# Sheet1.net
KiCad netlist of a schematic drawn in Altium Designer
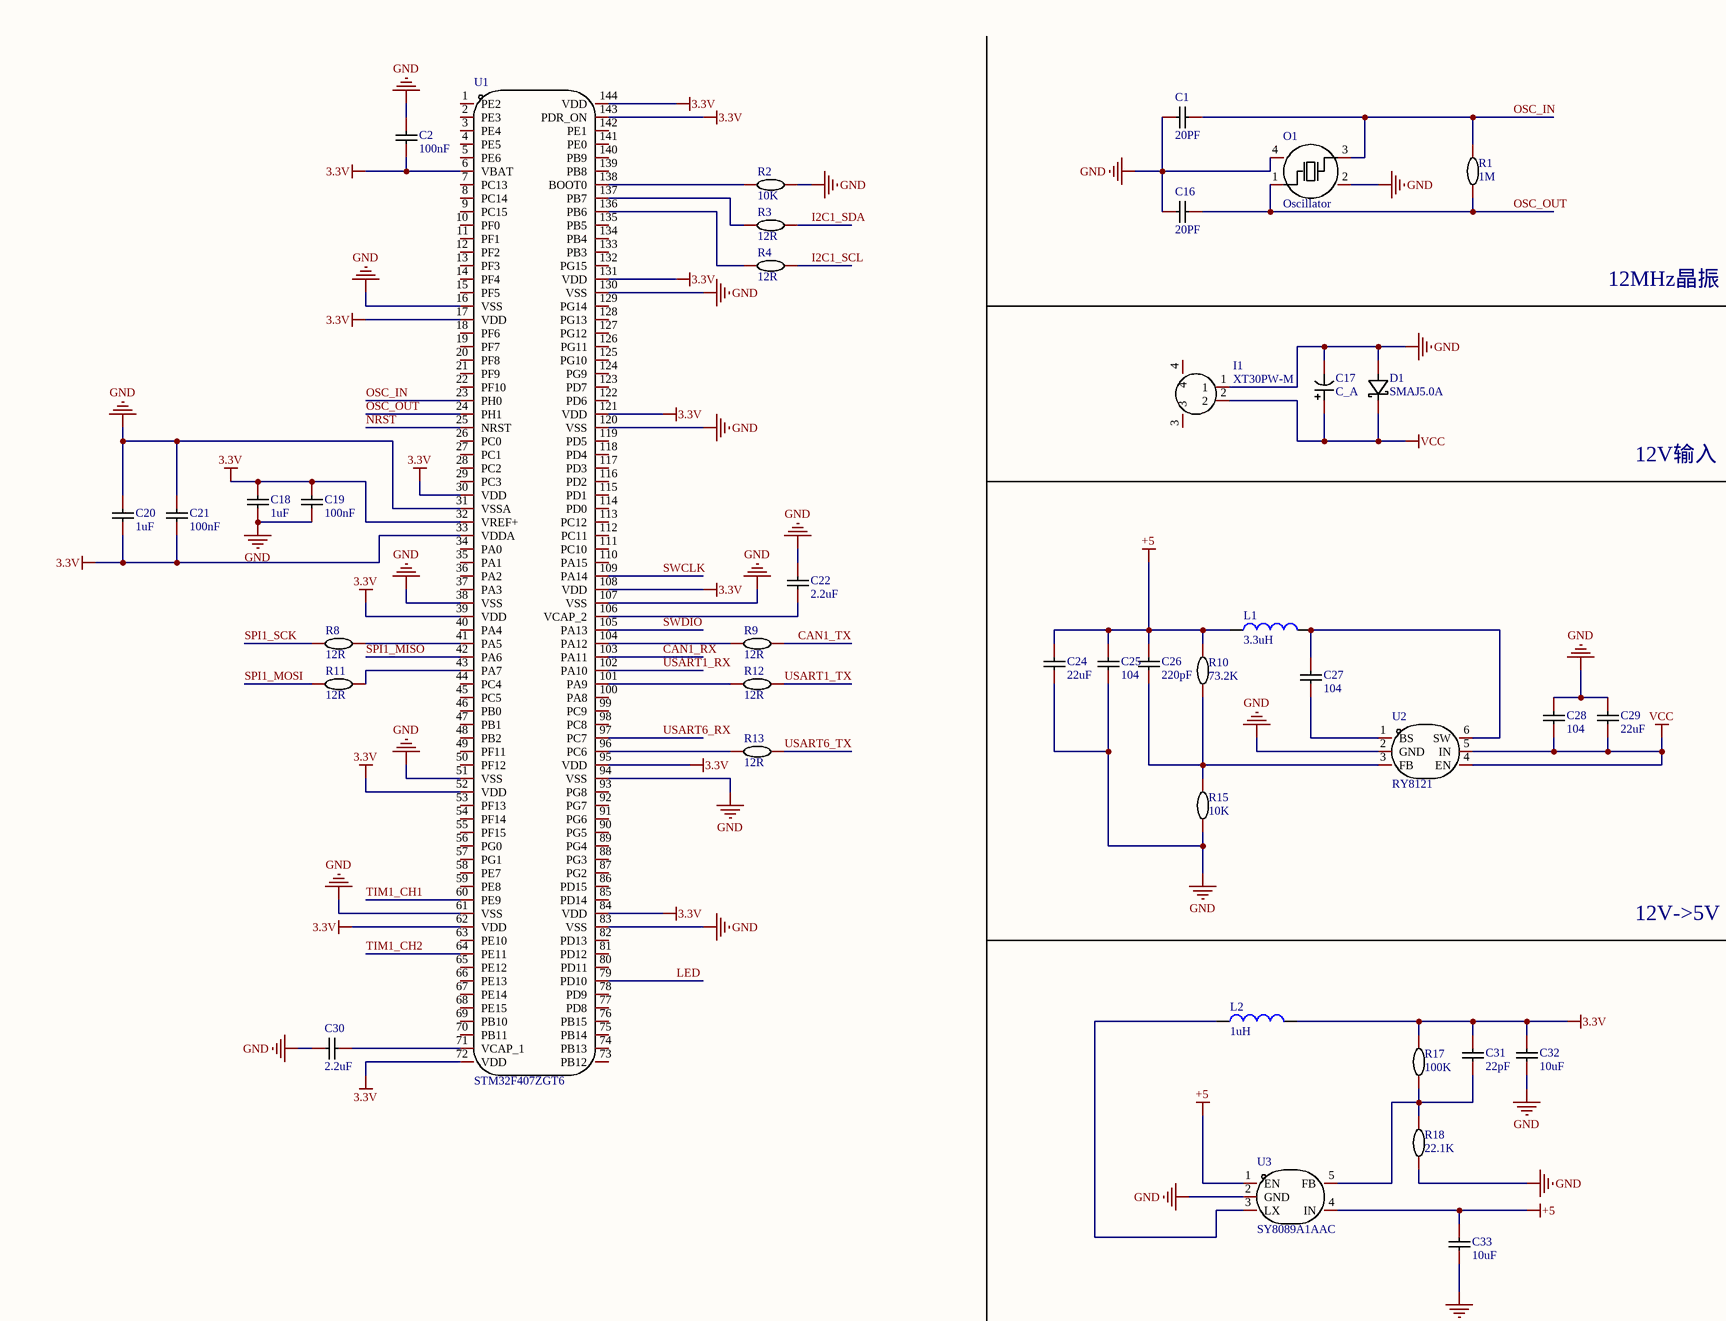
[diagram p0: Sheet1.SchDoc, top left]
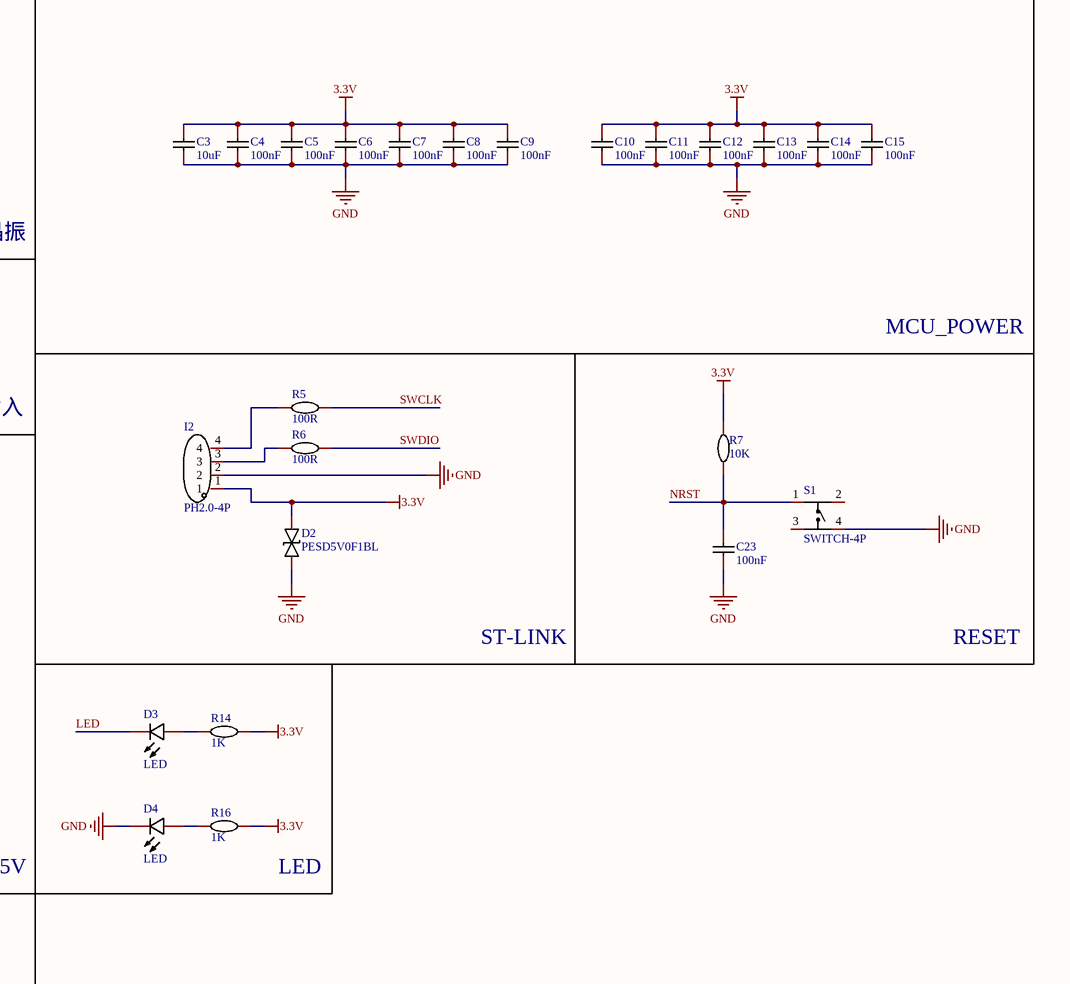
[diagram p1: Sheet1.SchDoc, top right]
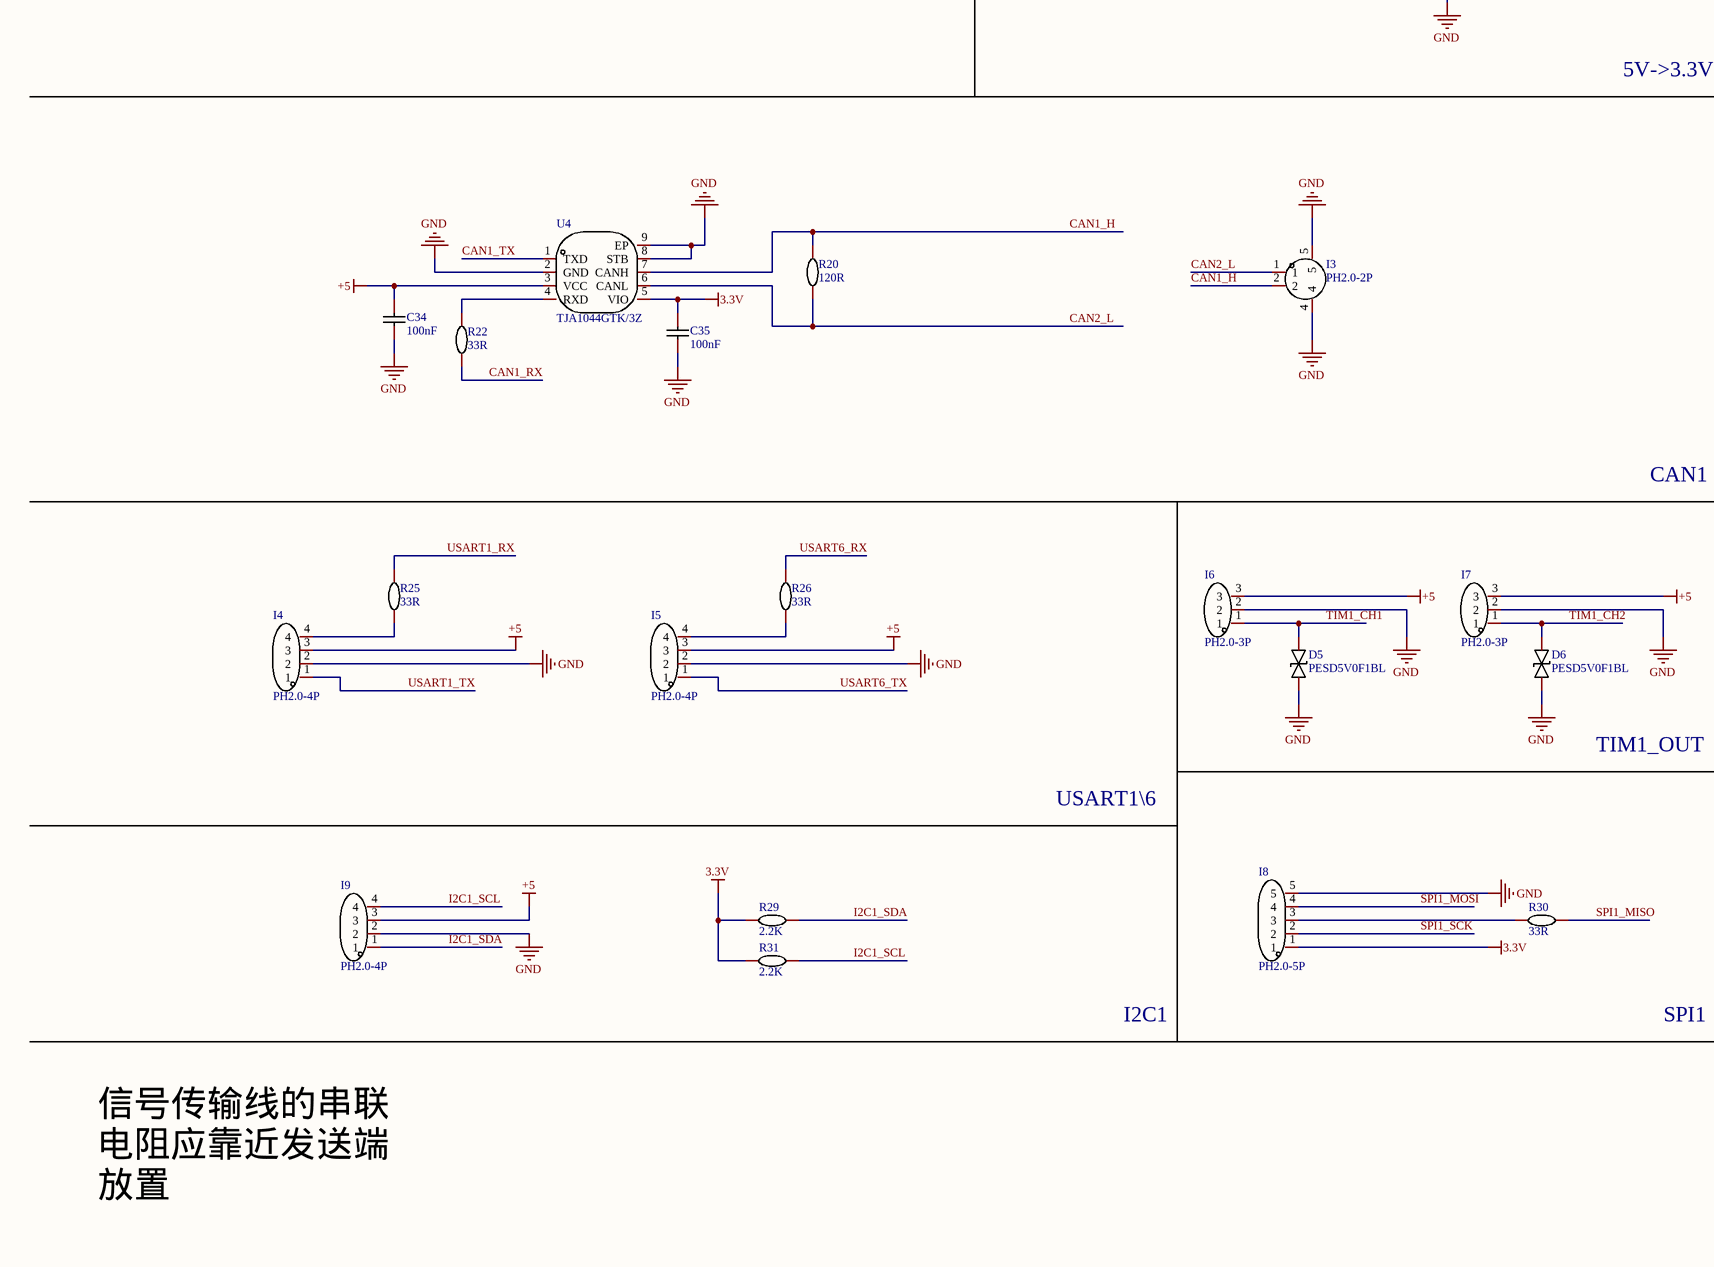
[diagram p2: Sheet1.SchDoc, bottom left]

(export (version "E")
  (design (tool "Eeschema 10.0.6"))
  (components
    (comp (ref "C1")
      (value "20PF")
      (footprint "C_0201")
      (description "贴片电容")
      (libsource (lib "My_Integrated_Library") (part "C"))
    )
    (comp (ref "C2")
      (value "100nF")
      (footprint "C_0201")
      (description "无极性贴片电容")
      (libsource (lib "My_Integrated_Library") (part "C"))
    )
    (comp (ref "C3")
      (value "10uF")
      (footprint "C_0201")
      (description "无极性贴片电容")
      (libsource (lib "My_Integrated_Library") (part "C"))
    )
    (comp (ref "C4")
      (value "100nF")
      (footprint "C_0201")
      (description "无极性贴片电容")
      (libsource (lib "My_Integrated_Library") (part "C"))
    )
    (comp (ref "C5")
      (value "100nF")
      (footprint "C_0201")
      (description "无极性贴片电容")
      (libsource (lib "My_Integrated_Library") (part "C"))
    )
    (comp (ref "C6")
      (value "100nF")
      (footprint "C_0201")
      (description "无极性贴片电容")
      (libsource (lib "My_Integrated_Library") (part "C"))
    )
    (comp (ref "C7")
      (value "100nF")
      (footprint "C_0201")
      (description "无极性贴片电容")
      (libsource (lib "My_Integrated_Library") (part "C"))
    )
    (comp (ref "C8")
      (value "100nF")
      (footprint "C_0201")
      (description "无极性贴片电容")
      (libsource (lib "My_Integrated_Library") (part "C"))
    )
    (comp (ref "C9")
      (value "100nF")
      (footprint "C_0201")
      (description "无极性贴片电容")
      (libsource (lib "My_Integrated_Library") (part "C"))
    )
    (comp (ref "C10")
      (value "100nF")
      (footprint "C_0201")
      (description "无极性贴片电容")
      (libsource (lib "My_Integrated_Library") (part "C"))
    )
    (comp (ref "C11")
      (value "100nF")
      (footprint "C_0201")
      (description "无极性贴片电容")
      (libsource (lib "My_Integrated_Library") (part "C"))
    )
    (comp (ref "C12")
      (value "100nF")
      (footprint "C_0201")
      (description "无极性贴片电容")
      (libsource (lib "My_Integrated_Library") (part "C"))
    )
    (comp (ref "C13")
      (value "100nF")
      (footprint "C_0201")
      (description "无极性贴片电容")
      (libsource (lib "My_Integrated_Library") (part "C"))
    )
    (comp (ref "C14")
      (value "100nF")
      (footprint "C_0201")
      (description "无极性贴片电容")
      (libsource (lib "My_Integrated_Library") (part "C"))
    )
    (comp (ref "C15")
      (value "100nF")
      (footprint "C_0201")
      (description "无极性贴片电容")
      (libsource (lib "My_Integrated_Library") (part "C"))
    )
    (comp (ref "C16")
      (value "20PF")
      (footprint "C_0201")
      (description "贴片电容")
      (libsource (lib "My_Integrated_Library") (part "C"))
    )
    (comp (ref "C17")
      (value "C_A")
      (footprint "C_8*10.5")
      (description "铝电解电容")
      (libsource (lib "My_Integrated_Library") (part "C_A"))
    )
    (comp (ref "C18")
      (value "1uF")
      (footprint "C_0201")
      (description "无极性贴片电容")
      (libsource (lib "My_Integrated_Library") (part "C"))
    )
    (comp (ref "C19")
      (value "100nF")
      (footprint "C_0201")
      (description "无极性贴片电容")
      (libsource (lib "My_Integrated_Library") (part "C"))
    )
    (comp (ref "C20")
      (value "1uF")
      (footprint "C_0201")
      (description "无极性贴片电容")
      (libsource (lib "My_Integrated_Library") (part "C"))
    )
    (comp (ref "C21")
      (value "100nF")
      (footprint "C_0201")
      (description "无极性贴片电容")
      (libsource (lib "My_Integrated_Library") (part "C"))
    )
    (comp (ref "C22")
      (value "2.2uF")
      (footprint "C_0201")
      (description "无极性贴片电容")
      (libsource (lib "My_Integrated_Library") (part "C"))
    )
    (comp (ref "C23")
      (value "100nF")
      (footprint "C_0402")
      (description "无极性贴片电容")
      (libsource (lib "My_Integrated_Library") (part "C"))
    )
    (comp (ref "C24")
      (value "22uF")
      (footprint "C_0402")
      (description "无极性贴片电容")
      (libsource (lib "My_Integrated_Library") (part "C"))
    )
    (comp (ref "C25")
      (value "104")
      (footprint "C_0402")
      (description "无极性贴片电容")
      (libsource (lib "My_Integrated_Library") (part "C"))
    )
    (comp (ref "C26")
      (value "220pF")
      (footprint "C_0603")
      (description "无极性贴片电容")
      (libsource (lib "My_Integrated_Library") (part "C"))
    )
    (comp (ref "C27")
      (value "104")
      (footprint "C_0402")
      (description "无极性贴片电容")
      (libsource (lib "My_Integrated_Library") (part "C"))
    )
    (comp (ref "C28")
      (value "104")
      (footprint "C_0402")
      (description "无极性贴片电容")
      (libsource (lib "My_Integrated_Library") (part "C"))
    )
    (comp (ref "C29")
      (value "22uF")
      (footprint "C_0402")
      (description "无极性贴片电容")
      (libsource (lib "My_Integrated_Library") (part "C"))
    )
    (comp (ref "C30")
      (value "2.2uF")
      (footprint "C_0201")
      (description "无极性贴片电容")
      (libsource (lib "My_Integrated_Library") (part "C"))
    )
    (comp (ref "C31")
      (value "22pF")
      (footprint "C_0603")
      (description "无极性贴片电容")
      (libsource (lib "My_Integrated_Library") (part "C"))
    )
    (comp (ref "C32")
      (value "10uF")
      (footprint "C_0603")
      (description "无极性贴片电容")
      (libsource (lib "My_Integrated_Library") (part "C"))
    )
    (comp (ref "C33")
      (value "10uF")
      (footprint "C_0603")
      (description "无极性贴片电容")
      (libsource (lib "My_Integrated_Library") (part "C"))
    )
    (comp (ref "C34")
      (value "100nF")
      (footprint "C_0402")
      (description "无极性贴片电容")
      (libsource (lib "My_Integrated_Library") (part "C"))
    )
    (comp (ref "C35")
      (value "100nF")
      (footprint "C_0402")
      (description "无极性贴片电容")
      (libsource (lib "My_Integrated_Library") (part "C"))
    )
    (comp (ref "D1")
      (value "SMAJ5.0A")
      (footprint "SMAJ5.0A")
      (description "TVS")
      (libsource (lib "My_Integrated_Library") (part "SMAJ5.0A"))
    )
    (comp (ref "D2")
      (value "PESD5V0F1BL")
      (footprint "PESD5V0F1BL")
      (description "双向TVS")
      (libsource (lib "My_Integrated_Library") (part "PESD5V0F1BL"))
    )
    (comp (ref "D3")
      (value "LED")
      (footprint "LED_0603")
      (description "发光二极管")
      (libsource (lib "My_Integrated_Library") (part "LED"))
    )
    (comp (ref "D4")
      (value "LED")
      (footprint "LED_0603")
      (description "发光二极管")
      (libsource (lib "My_Integrated_Library") (part "LED"))
    )
    (comp (ref "D5")
      (value "PESD5V0F1BL")
      (footprint "PESD5V0F1BL")
      (description "双向TVS")
      (libsource (lib "My_Integrated_Library") (part "PESD5V0F1BL"))
    )
    (comp (ref "D6")
      (value "PESD5V0F1BL")
      (footprint "PESD5V0F1BL")
      (description "双向TVS")
      (libsource (lib "My_Integrated_Library") (part "PESD5V0F1BL"))
    )
    (comp (ref "I1")
      (value "XT30PW-M")
      (footprint "XT30PW-M")
      (description "卧式公头")
      (libsource (lib "My_Integrated_Library") (part "XT30PW-M"))
    )
    (comp (ref "I2")
      (value "PH2.0-4P")
      (footprint "PH2.0-4P")
      (libsource (lib "My_Integrated_Library") (part "PH2.0-4P"))
    )
    (comp (ref "I3")
      (value "PH2.0-2P")
      (footprint "PH2.0-2P")
      (description "卧贴")
      (libsource (lib "My_Integrated_Library") (part "PH2.0-2P"))
    )
    (comp (ref "I4")
      (value "PH2.0-4P")
      (footprint "PH2.0-4P")
      (libsource (lib "My_Integrated_Library") (part "PH2.0-4P"))
    )
    (comp (ref "I5")
      (value "PH2.0-4P")
      (footprint "PH2.0-4P")
      (libsource (lib "My_Integrated_Library") (part "PH2.0-4P"))
    )
    (comp (ref "I6")
      (value "PH2.0-3P")
      (footprint "PH2.0-3P")
      (description "PH3.0-3P弯插")
      (libsource (lib "My_Integrated_Library") (part "PH2.0-3P"))
    )
    (comp (ref "I7")
      (value "PH2.0-3P")
      (footprint "PH2.0-3P")
      (description "PH3.0-3P弯插")
      (libsource (lib "My_Integrated_Library") (part "PH2.0-3P"))
    )
    (comp (ref "I8")
      (value "PH2.0-5P")
      (footprint "PH2.0-5P")
      (description "弯插")
      (libsource (lib "My_Integrated_Library") (part "PH2.0-5P"))
    )
    (comp (ref "I9")
      (value "PH2.0-4P")
      (footprint "PH2.0-4P")
      (libsource (lib "My_Integrated_Library") (part "PH2.0-4P"))
    )
    (comp (ref "L1")
      (value "3.3uH")
      (footprint "L_0402")
      (description "SMD电感4.2*4.2*1.8")
      (libsource (lib "My_Integrated_Library") (part "L"))
    )
    (comp (ref "L2")
      (value "1uH")
      (footprint "L_0402")
      (description "SMD电感4.2*4.2*1.8")
      (libsource (lib "My_Integrated_Library") (part "L"))
    )
    (comp (ref "O1")
      (value "Oscillator")
      (footprint "Oscillator")
      (description "晶振")
      (libsource (lib "My_Integrated_Library") (part "Oscillator"))
    )
    (comp (ref "R1")
      (value "1M")
      (footprint "R_0201")
      (description "电阻")
      (libsource (lib "My_Integrated_Library") (part "R"))
    )
    (comp (ref "R2")
      (value "10K")
      (footprint "R_0402")
      (description "贴片电阻")
      (libsource (lib "My_Integrated_Library") (part "R"))
    )
    (comp (ref "R3")
      (value "12R")
      (footprint "R_0402")
      (description "贴片电阻")
      (libsource (lib "My_Integrated_Library") (part "R"))
    )
    (comp (ref "R4")
      (value "12R")
      (footprint "R_0402")
      (description "贴片电阻")
      (libsource (lib "My_Integrated_Library") (part "R"))
    )
    (comp (ref "R5")
      (value "100R")
      (footprint "R_0201")
      (description "贴片电阻")
      (libsource (lib "My_Integrated_Library") (part "R"))
    )
    (comp (ref "R6")
      (value "100R")
      (footprint "R_0201")
      (description "贴片电阻")
      (libsource (lib "My_Integrated_Library") (part "R"))
    )
    (comp (ref "R7")
      (value "10K")
      (footprint "R_0402")
      (description "贴片电阻")
      (libsource (lib "My_Integrated_Library") (part "R"))
    )
    (comp (ref "R8")
      (value "12R")
      (footprint "R_0402")
      (description "贴片电阻")
      (libsource (lib "My_Integrated_Library") (part "R"))
    )
    (comp (ref "R9")
      (value "12R")
      (footprint "R_0402")
      (description "贴片电阻")
      (libsource (lib "My_Integrated_Library") (part "R"))
    )
    (comp (ref "R10")
      (value "73.2K")
      (footprint "R_0603")
      (description "贴片电阻")
      (libsource (lib "My_Integrated_Library") (part "R"))
    )
    (comp (ref "R11")
      (value "12R")
      (footprint "R_0402")
      (description "贴片电阻")
      (libsource (lib "My_Integrated_Library") (part "R"))
    )
    (comp (ref "R12")
      (value "12R")
      (footprint "R_0402")
      (description "贴片电阻")
      (libsource (lib "My_Integrated_Library") (part "R"))
    )
    (comp (ref "R13")
      (value "12R")
      (footprint "R_0402")
      (description "贴片电阻")
      (libsource (lib "My_Integrated_Library") (part "R"))
    )
    (comp (ref "R14")
      (value "1K")
      (footprint "R_0603")
      (description "贴片电阻")
      (libsource (lib "My_Integrated_Library") (part "R"))
    )
    (comp (ref "R15")
      (value "10K")
      (footprint "R_0603")
      (description "贴片电阻")
      (libsource (lib "My_Integrated_Library") (part "R"))
    )
    (comp (ref "R16")
      (value "1K")
      (footprint "R_0603")
      (description "贴片电阻")
      (libsource (lib "My_Integrated_Library") (part "R"))
    )
    (comp (ref "R17")
      (value "100K")
      (footprint "R_0603")
      (description "贴片电阻")
      (libsource (lib "My_Integrated_Library") (part "R"))
    )
    (comp (ref "R18")
      (value "22.1K")
      (footprint "R_0603")
      (description "贴片电阻")
      (libsource (lib "My_Integrated_Library") (part "R"))
    )
    (comp (ref "R20")
      (value "120R")
      (footprint "R_0402")
      (description "贴片电阻")
      (libsource (lib "My_Integrated_Library") (part "R"))
    )
    (comp (ref "R22")
      (value "33R")
      (footprint "R_0402")
      (description "贴片电阻")
      (libsource (lib "My_Integrated_Library") (part "R"))
    )
    (comp (ref "R25")
      (value "33R")
      (footprint "R_0402")
      (description "贴片电阻")
      (libsource (lib "My_Integrated_Library") (part "R"))
    )
    (comp (ref "R26")
      (value "33R")
      (footprint "R_0402")
      (description "贴片电阻")
      (libsource (lib "My_Integrated_Library") (part "R"))
    )
    (comp (ref "R29")
      (value "2.2K")
      (footprint "R_0402")
      (description "贴片电阻")
      (libsource (lib "My_Integrated_Library") (part "R"))
    )
    (comp (ref "R30")
      (value "33R")
      (footprint "R_0402")
      (description "贴片电阻")
      (libsource (lib "My_Integrated_Library") (part "R"))
    )
    (comp (ref "R31")
      (value "2.2K")
      (footprint "R_0402")
      (description "贴片电阻")
      (libsource (lib "My_Integrated_Library") (part "R"))
    )
    (comp (ref "S1")
      (value "SWITCH-4P")
      (footprint "SWITCH-4P")
      (libsource (lib "My_Integrated_Library") (part "SWITCH-4P"))
    )
    (comp (ref "U1")
      (value "STM32F407ZGT6")
      (footprint "STM32F407ZGT6")
      (libsource (lib "My_Integrated_Library") (part "STM32F407ZGT6"))
    )
    (comp (ref "U2")
      (value "RY8121")
      (footprint "RY8121")
      (description "DC-DC")
      (libsource (lib "My_Integrated_Library") (part "RY8121"))
    )
    (comp (ref "U3")
      (value "SY8089A1AAC")
      (footprint "SY8089A1AAC")
      (description "DC-DC")
      (libsource (lib "My_Integrated_Library") (part "SY8089A1AAC"))
    )
    (comp (ref "U4")
      (value "TJA1044GTK/3Z")
      (footprint "TJA1044GTK/3Z")
      (description "CAN")
      (libsource (lib "My_Integrated_Library") (part "TJA1044GTK/3Z"))
    )
  )
  (nets
    (net (code "1") (name "+5") (class "Default")
      (node (ref "C24") (pin "2") (pinfunction "2_2") (pintype "passive"))
      (node (ref "C25") (pin "2") (pinfunction "2_2") (pintype "passive"))
      (node (ref "C26") (pin "2") (pinfunction "2_2") (pintype "passive"))
      (node (ref "C33") (pin "2") (pinfunction "2_2") (pintype "passive"))
      (node (ref "C34") (pin "2") (pinfunction "2_2") (pintype "passive"))
      (node (ref "I4") (pin "3") (pinfunction "3_3") (pintype "passive"))
      (node (ref "I5") (pin "3") (pinfunction "3_3") (pintype "passive"))
      (node (ref "I6") (pin "3") (pinfunction "3_3") (pintype "passive"))
      (node (ref "I7") (pin "3") (pinfunction "3_3") (pintype "passive"))
      (node (ref "I9") (pin "3") (pinfunction "3_3") (pintype "passive"))
      (node (ref "L1") (pin "1") (pinfunction "1_1") (pintype "passive"))
      (node (ref "R10") (pin "2") (pinfunction "2_2") (pintype "passive"))
      (node (ref "U3") (pin "1") (pinfunction "EN_1") (pintype "passive"))
      (node (ref "U3") (pin "4") (pinfunction "IN_4") (pintype "passive"))
      (node (ref "U4") (pin "3") (pinfunction "VCC_3") (pintype "passive"))
    )
    (net (code "2") (name "/CAN1_H") (class "Default")
      (node (ref "I3") (pin "2") (pinfunction "2_2") (pintype "passive"))
      (node (ref "R20") (pin "2") (pinfunction "2_2") (pintype "passive"))
      (node (ref "U4") (pin "7") (pinfunction "CANH_7") (pintype "passive"))
    )
    (net (code "3") (name "/CAN1_RX") (class "Default")
      (node (ref "R22") (pin "1") (pinfunction "1_1") (pintype "passive"))
      (node (ref "U1") (pin "103") (pinfunction "PA11_103") (pintype "passive"))
    )
    (net (code "4") (name "/CAN1_TX") (class "Default")
      (node (ref "R9") (pin "1") (pinfunction "1_1") (pintype "passive"))
      (node (ref "U4") (pin "1") (pinfunction "TXD_1") (pintype "passive"))
    )
    (net (code "5") (name "/CAN2_L") (class "Default")
      (node (ref "I3") (pin "1") (pinfunction "1_1") (pintype "passive"))
      (node (ref "R20") (pin "1") (pinfunction "1_1") (pintype "passive"))
      (node (ref "U4") (pin "6") (pinfunction "CANL_6") (pintype "passive"))
    )
    (net (code "6") (name "/I2C1_SCL") (class "Default")
      (node (ref "I9") (pin "4") (pinfunction "4_4") (pintype "passive"))
      (node (ref "R31") (pin "1") (pinfunction "1_1") (pintype "passive"))
      (node (ref "R4") (pin "1") (pinfunction "1_1") (pintype "passive"))
    )
    (net (code "7") (name "/I2C1_SDA") (class "Default")
      (node (ref "I9") (pin "1") (pinfunction "1_1") (pintype "passive"))
      (node (ref "R29") (pin "1") (pinfunction "1_1") (pintype "passive"))
      (node (ref "R3") (pin "1") (pinfunction "1_1") (pintype "passive"))
    )
    (net (code "8") (name "/LED") (class "Default")
      (node (ref "D3") (pin "1") (pinfunction "K_1") (pintype "passive"))
      (node (ref "U1") (pin "79") (pinfunction "PD10_79") (pintype "passive"))
    )
    (net (code "9") (name "/NRST") (class "Default")
      (node (ref "C23") (pin "2") (pinfunction "2_2") (pintype "passive"))
      (node (ref "R7") (pin "1") (pinfunction "1_1") (pintype "passive"))
      (node (ref "S1") (pin "1") (pinfunction "1_1") (pintype "passive"))
      (node (ref "U1") (pin "25") (pinfunction "NRST_25") (pintype "passive"))
    )
    (net (code "10") (name "/OSC_IN") (class "Default")
      (node (ref "C1") (pin "2") (pinfunction "2_2") (pintype "passive"))
      (node (ref "O1") (pin "3") (pinfunction "OSC2_3") (pintype "passive"))
      (node (ref "R1") (pin "2") (pinfunction "2_2") (pintype "passive"))
      (node (ref "U1") (pin "23") (pinfunction "PH0_23") (pintype "passive"))
    )
    (net (code "11") (name "/OSC_OUT") (class "Default")
      (node (ref "C16") (pin "2") (pinfunction "2_2") (pintype "passive"))
      (node (ref "O1") (pin "1") (pinfunction "OSC1_1") (pintype "passive"))
      (node (ref "R1") (pin "1") (pinfunction "1_1") (pintype "passive"))
      (node (ref "U1") (pin "24") (pinfunction "PH1_24") (pintype "passive"))
    )
    (net (code "12") (name "/SPI1_MISO") (class "Default")
      (node (ref "R30") (pin "2") (pinfunction "2_2") (pintype "passive"))
      (node (ref "U1") (pin "42") (pinfunction "PA6_42") (pintype "passive"))
    )
    (net (code "13") (name "/SPI1_MOSI") (class "Default")
      (node (ref "I8") (pin "4") (pinfunction "4_4") (pintype "passive"))
      (node (ref "R11") (pin "2") (pinfunction "2_2") (pintype "passive"))
    )
    (net (code "14") (name "/SPI1_SCK") (class "Default")
      (node (ref "I8") (pin "2") (pinfunction "2_2") (pintype "passive"))
      (node (ref "R8") (pin "2") (pinfunction "2_2") (pintype "passive"))
    )
    (net (code "15") (name "/SWCLK") (class "Default")
      (node (ref "R5") (pin "2") (pinfunction "2_2") (pintype "passive"))
      (node (ref "U1") (pin "109") (pinfunction "PA14_109") (pintype "passive"))
    )
    (net (code "16") (name "/SWDIO") (class "Default")
      (node (ref "R6") (pin "2") (pinfunction "2_2") (pintype "passive"))
      (node (ref "U1") (pin "105") (pinfunction "PA13_105") (pintype "passive"))
    )
    (net (code "17") (name "/TIM1_CH1") (class "Default")
      (node (ref "D5") (pin "1") (pinfunction "1_1") (pintype "passive"))
      (node (ref "I6") (pin "1") (pinfunction "1_1") (pintype "passive"))
      (node (ref "U1") (pin "60") (pinfunction "PE9_60") (pintype "passive"))
    )
    (net (code "18") (name "/TIM1_CH2") (class "Default")
      (node (ref "D6") (pin "1") (pinfunction "1_1") (pintype "passive"))
      (node (ref "I7") (pin "1") (pinfunction "1_1") (pintype "passive"))
      (node (ref "U1") (pin "64") (pinfunction "PE11_64") (pintype "passive"))
    )
    (net (code "19") (name "/USART1_RX") (class "Default")
      (node (ref "R25") (pin "2") (pinfunction "2_2") (pintype "passive"))
      (node (ref "U1") (pin "102") (pinfunction "PA10_102") (pintype "passive"))
    )
    (net (code "20") (name "/USART1_TX") (class "Default")
      (node (ref "I4") (pin "1") (pinfunction "1_1") (pintype "passive"))
      (node (ref "R12") (pin "1") (pinfunction "1_1") (pintype "passive"))
    )
    (net (code "21") (name "/USART6_RX") (class "Default")
      (node (ref "R26") (pin "2") (pinfunction "2_2") (pintype "passive"))
      (node (ref "U1") (pin "97") (pinfunction "PC7_97") (pintype "passive"))
    )
    (net (code "22") (name "/USART6_TX") (class "Default")
      (node (ref "I5") (pin "1") (pinfunction "1_1") (pintype "passive"))
      (node (ref "R13") (pin "1") (pinfunction "1_1") (pintype "passive"))
    )
    (net (code "23") (name "3.3V") (class "Default")
      (node (ref "C10") (pin "1") (pinfunction "1_1") (pintype "passive"))
      (node (ref "C11") (pin "1") (pinfunction "1_1") (pintype "passive"))
      (node (ref "C12") (pin "1") (pinfunction "1_1") (pintype "passive"))
      (node (ref "C13") (pin "1") (pinfunction "1_1") (pintype "passive"))
      (node (ref "C14") (pin "1") (pinfunction "1_1") (pintype "passive"))
      (node (ref "C15") (pin "1") (pinfunction "1_1") (pintype "passive"))
      (node (ref "C18") (pin "2") (pinfunction "2_2") (pintype "passive"))
      (node (ref "C19") (pin "2") (pinfunction "2_2") (pintype "passive"))
      (node (ref "C2") (pin "2") (pinfunction "2_2") (pintype "passive"))
      (node (ref "C20") (pin "1") (pinfunction "1_1") (pintype "passive"))
      (node (ref "C21") (pin "1") (pinfunction "1_1") (pintype "passive"))
      (node (ref "C3") (pin "1") (pinfunction "1_1") (pintype "passive"))
      (node (ref "C31") (pin "2") (pinfunction "2_2") (pintype "passive"))
      (node (ref "C32") (pin "2") (pinfunction "2_2") (pintype "passive"))
      (node (ref "C35") (pin "2") (pinfunction "2_2") (pintype "passive"))
      (node (ref "C4") (pin "1") (pinfunction "1_1") (pintype "passive"))
      (node (ref "C5") (pin "1") (pinfunction "1_1") (pintype "passive"))
      (node (ref "C6") (pin "1") (pinfunction "1_1") (pintype "passive"))
      (node (ref "C7") (pin "1") (pinfunction "1_1") (pintype "passive"))
      (node (ref "C8") (pin "1") (pinfunction "1_1") (pintype "passive"))
      (node (ref "C9") (pin "1") (pinfunction "1_1") (pintype "passive"))
      (node (ref "D2") (pin "2") (pinfunction "2_2") (pintype "passive"))
      (node (ref "I2") (pin "1") (pinfunction "1_1") (pintype "passive"))
      (node (ref "I8") (pin "1") (pinfunction "1_1") (pintype "passive"))
      (node (ref "L2") (pin "2") (pinfunction "2_2") (pintype "passive"))
      (node (ref "R14") (pin "2") (pinfunction "2_2") (pintype "passive"))
      (node (ref "R16") (pin "2") (pinfunction "2_2") (pintype "passive"))
      (node (ref "R17") (pin "2") (pinfunction "2_2") (pintype "passive"))
      (node (ref "R29") (pin "2") (pinfunction "2_2") (pintype "passive"))
      (node (ref "R31") (pin "2") (pinfunction "2_2") (pintype "passive"))
      (node (ref "R7") (pin "2") (pinfunction "2_2") (pintype "passive"))
      (node (ref "U1") (pin "108") (pinfunction "VDD_108") (pintype "passive"))
      (node (ref "U1") (pin "121") (pinfunction "VDD_121") (pintype "passive"))
      (node (ref "U1") (pin "131") (pinfunction "VDD_131") (pintype "passive"))
      (node (ref "U1") (pin "143") (pinfunction "PDR_ON_143") (pintype "passive"))
      (node (ref "U1") (pin "144") (pinfunction "VDD_144") (pintype "passive"))
      (node (ref "U1") (pin "17") (pinfunction "VDD_17") (pintype "passive"))
      (node (ref "U1") (pin "30") (pinfunction "VDD_30") (pintype "passive"))
      (node (ref "U1") (pin "32") (pinfunction "VREF+_32") (pintype "passive"))
      (node (ref "U1") (pin "33") (pinfunction "VDDA_33") (pintype "passive"))
      (node (ref "U1") (pin "39") (pinfunction "VDD_39") (pintype "passive"))
      (node (ref "U1") (pin "52") (pinfunction "VDD_52") (pintype "passive"))
      (node (ref "U1") (pin "6") (pinfunction "VBAT_6") (pintype "passive"))
      (node (ref "U1") (pin "62") (pinfunction "VDD_62") (pintype "passive"))
      (node (ref "U1") (pin "72") (pinfunction "VDD_72") (pintype "passive"))
      (node (ref "U1") (pin "84") (pinfunction "VDD_84") (pintype "passive"))
      (node (ref "U1") (pin "95") (pinfunction "VDD_95") (pintype "passive"))
      (node (ref "U4") (pin "5") (pinfunction "VIO_5") (pintype "passive"))
    )
    (net (code "24") (name "GND") (class "Default")
      (node (ref "C1") (pin "1") (pinfunction "1_1") (pintype "passive"))
      (node (ref "C10") (pin "2") (pinfunction "2_2") (pintype "passive"))
      (node (ref "C11") (pin "2") (pinfunction "2_2") (pintype "passive"))
      (node (ref "C12") (pin "2") (pinfunction "2_2") (pintype "passive"))
      (node (ref "C13") (pin "2") (pinfunction "2_2") (pintype "passive"))
      (node (ref "C14") (pin "2") (pinfunction "2_2") (pintype "passive"))
      (node (ref "C15") (pin "2") (pinfunction "2_2") (pintype "passive"))
      (node (ref "C16") (pin "1") (pinfunction "1_1") (pintype "passive"))
      (node (ref "C17") (pin "2") (pinfunction "2_2") (pintype "passive"))
      (node (ref "C18") (pin "1") (pinfunction "1_1") (pintype "passive"))
      (node (ref "C19") (pin "1") (pinfunction "1_1") (pintype "passive"))
      (node (ref "C2") (pin "1") (pinfunction "1_1") (pintype "passive"))
      (node (ref "C20") (pin "2") (pinfunction "2_2") (pintype "passive"))
      (node (ref "C21") (pin "2") (pinfunction "2_2") (pintype "passive"))
      (node (ref "C22") (pin "2") (pinfunction "2_2") (pintype "passive"))
      (node (ref "C23") (pin "1") (pinfunction "1_1") (pintype "passive"))
      (node (ref "C24") (pin "1") (pinfunction "1_1") (pintype "passive"))
      (node (ref "C25") (pin "1") (pinfunction "1_1") (pintype "passive"))
      (node (ref "C28") (pin "2") (pinfunction "2_2") (pintype "passive"))
      (node (ref "C29") (pin "2") (pinfunction "2_2") (pintype "passive"))
      (node (ref "C3") (pin "2") (pinfunction "2_2") (pintype "passive"))
      (node (ref "C30") (pin "1") (pinfunction "1_1") (pintype "passive"))
      (node (ref "C32") (pin "1") (pinfunction "1_1") (pintype "passive"))
      (node (ref "C33") (pin "1") (pinfunction "1_1") (pintype "passive"))
      (node (ref "C34") (pin "1") (pinfunction "1_1") (pintype "passive"))
      (node (ref "C35") (pin "1") (pinfunction "1_1") (pintype "passive"))
      (node (ref "C4") (pin "2") (pinfunction "2_2") (pintype "passive"))
      (node (ref "C5") (pin "2") (pinfunction "2_2") (pintype "passive"))
      (node (ref "C6") (pin "2") (pinfunction "2_2") (pintype "passive"))
      (node (ref "C7") (pin "2") (pinfunction "2_2") (pintype "passive"))
      (node (ref "C8") (pin "2") (pinfunction "2_2") (pintype "passive"))
      (node (ref "C9") (pin "2") (pinfunction "2_2") (pintype "passive"))
      (node (ref "D1") (pin "2") (pinfunction "A_2") (pintype "passive"))
      (node (ref "D2") (pin "1") (pinfunction "1_1") (pintype "passive"))
      (node (ref "D4") (pin "1") (pinfunction "K_1") (pintype "passive"))
      (node (ref "D5") (pin "2") (pinfunction "2_2") (pintype "passive"))
      (node (ref "D6") (pin "2") (pinfunction "2_2") (pintype "passive"))
      (node (ref "I1") (pin "1") (pinfunction "1_1") (pintype "passive"))
      (node (ref "I2") (pin "2") (pinfunction "2_2") (pintype "passive"))
      (node (ref "I3") (pin "4") (pinfunction "4_4") (pintype "passive"))
      (node (ref "I3") (pin "5") (pinfunction "5_5") (pintype "passive"))
      (node (ref "I4") (pin "2") (pinfunction "2_2") (pintype "passive"))
      (node (ref "I5") (pin "2") (pinfunction "2_2") (pintype "passive"))
      (node (ref "I6") (pin "2") (pinfunction "2_2") (pintype "passive"))
      (node (ref "I7") (pin "2") (pinfunction "2_2") (pintype "passive"))
      (node (ref "I8") (pin "5") (pinfunction "5_5") (pintype "passive"))
      (node (ref "I9") (pin "2") (pinfunction "2_2") (pintype "passive"))
      (node (ref "O1") (pin "2") (pinfunction "GND_2") (pintype "passive"))
      (node (ref "O1") (pin "4") (pinfunction "GND_4") (pintype "passive"))
      (node (ref "R15") (pin "1") (pinfunction "1_1") (pintype "passive"))
      (node (ref "R18") (pin "1") (pinfunction "1_1") (pintype "passive"))
      (node (ref "R2") (pin "1") (pinfunction "1_1") (pintype "passive"))
      (node (ref "S1") (pin "4") (pinfunction "4_4") (pintype "passive"))
      (node (ref "U1") (pin "107") (pinfunction "VSS_107") (pintype "passive"))
      (node (ref "U1") (pin "120") (pinfunction "VSS_120") (pintype "passive"))
      (node (ref "U1") (pin "130") (pinfunction "VSS_130") (pintype "passive"))
      (node (ref "U1") (pin "16") (pinfunction "VSS_16") (pintype "passive"))
      (node (ref "U1") (pin "31") (pinfunction "VSSA_31") (pintype "passive"))
      (node (ref "U1") (pin "38") (pinfunction "VSS_38") (pintype "passive"))
      (node (ref "U1") (pin "51") (pinfunction "VSS_51") (pintype "passive"))
      (node (ref "U1") (pin "61") (pinfunction "VSS_61") (pintype "passive"))
      (node (ref "U1") (pin "83") (pinfunction "VSS_83") (pintype "passive"))
      (node (ref "U1") (pin "94") (pinfunction "VSS_94") (pintype "passive"))
      (node (ref "U2") (pin "2") (pinfunction "GND_2") (pintype "passive"))
      (node (ref "U3") (pin "2") (pinfunction "GND_2") (pintype "passive"))
      (node (ref "U4") (pin "2") (pinfunction "GND_2") (pintype "passive"))
      (node (ref "U4") (pin "8") (pinfunction "STB_8") (pintype "passive"))
      (node (ref "U4") (pin "9") (pinfunction "EP_9") (pintype "passive"))
    )
    (net (code "25") (name "Net-(D3-A)") (class "Default")
      (node (ref "D3") (pin "2") (pinfunction "A_2") (pintype "passive"))
      (node (ref "R14") (pin "1") (pinfunction "1_1") (pintype "passive"))
    )
    (net (code "26") (name "Net-(D4-A)") (class "Default")
      (node (ref "D4") (pin "2") (pinfunction "A_2") (pintype "passive"))
      (node (ref "R16") (pin "1") (pinfunction "1_1") (pintype "passive"))
    )
    (net (code "27") (name "Net-(I2-Pad3)") (class "Default")
      (node (ref "I2") (pin "3") (pinfunction "3_3") (pintype "passive"))
      (node (ref "R6") (pin "1") (pinfunction "1_1") (pintype "passive"))
    )
    (net (code "28") (name "Net-(I2-Pad4)") (class "Default")
      (node (ref "I2") (pin "4") (pinfunction "4_4") (pintype "passive"))
      (node (ref "R5") (pin "1") (pinfunction "1_1") (pintype "passive"))
    )
    (net (code "29") (name "Net-(I4-Pad4)") (class "Default")
      (node (ref "I4") (pin "4") (pinfunction "4_4") (pintype "passive"))
      (node (ref "R25") (pin "1") (pinfunction "1_1") (pintype "passive"))
    )
    (net (code "30") (name "Net-(I5-Pad4)") (class "Default")
      (node (ref "I5") (pin "4") (pinfunction "4_4") (pintype "passive"))
      (node (ref "R26") (pin "1") (pinfunction "1_1") (pintype "passive"))
    )
    (net (code "31") (name "Net-(I8-Pad3)") (class "Default")
      (node (ref "I8") (pin "3") (pinfunction "3_3") (pintype "passive"))
      (node (ref "R30") (pin "1") (pinfunction "1_1") (pintype "passive"))
    )
    (net (code "32") (name "Net-(U1-BOOT0)") (class "Default")
      (node (ref "R2") (pin "2") (pinfunction "2_2") (pintype "passive"))
      (node (ref "U1") (pin "138") (pinfunction "BOOT0_138") (pintype "passive"))
    )
    (net (code "33") (name "Net-(U1-PA5)") (class "Default")
      (node (ref "R8") (pin "1") (pinfunction "1_1") (pintype "passive"))
      (node (ref "U1") (pin "41") (pinfunction "PA5_41") (pintype "passive"))
    )
    (net (code "34") (name "Net-(U1-PA7)") (class "Default")
      (node (ref "R11") (pin "1") (pinfunction "1_1") (pintype "passive"))
      (node (ref "U1") (pin "43") (pinfunction "PA7_43") (pintype "passive"))
    )
    (net (code "35") (name "Net-(U1-PA9)") (class "Default")
      (node (ref "R12") (pin "2") (pinfunction "2_2") (pintype "passive"))
      (node (ref "U1") (pin "101") (pinfunction "PA9_101") (pintype "passive"))
    )
    (net (code "36") (name "Net-(U1-PA12)") (class "Default")
      (node (ref "R9") (pin "2") (pinfunction "2_2") (pintype "passive"))
      (node (ref "U1") (pin "104") (pinfunction "PA12_104") (pintype "passive"))
    )
    (net (code "37") (name "Net-(U1-PB6)") (class "Default")
      (node (ref "R4") (pin "2") (pinfunction "2_2") (pintype "passive"))
      (node (ref "U1") (pin "136") (pinfunction "PB6_136") (pintype "passive"))
    )
    (net (code "38") (name "Net-(U1-PB7)") (class "Default")
      (node (ref "R3") (pin "2") (pinfunction "2_2") (pintype "passive"))
      (node (ref "U1") (pin "137") (pinfunction "PB7_137") (pintype "passive"))
    )
    (net (code "39") (name "Net-(U1-PC6)") (class "Default")
      (node (ref "R13") (pin "2") (pinfunction "2_2") (pintype "passive"))
      (node (ref "U1") (pin "96") (pinfunction "PC6_96") (pintype "passive"))
    )
    (net (code "40") (name "Net-(U1-VCAP_1)") (class "Default")
      (node (ref "C30") (pin "2") (pinfunction "2_2") (pintype "passive"))
      (node (ref "U1") (pin "71") (pinfunction "VCAP_1_71") (pintype "passive"))
    )
    (net (code "41") (name "Net-(U1-VCAP_2)") (class "Default")
      (node (ref "C22") (pin "1") (pinfunction "1_1") (pintype "passive"))
      (node (ref "U1") (pin "106") (pinfunction "VCAP_2_106") (pintype "passive"))
    )
    (net (code "42") (name "Net-(U2-BS)") (class "Default")
      (node (ref "C27") (pin "1") (pinfunction "1_1") (pintype "passive"))
      (node (ref "U2") (pin "1") (pinfunction "BS_1") (pintype "passive"))
    )
    (net (code "43") (name "Net-(U2-FB)") (class "Default")
      (node (ref "C26") (pin "1") (pinfunction "1_1") (pintype "passive"))
      (node (ref "R10") (pin "1") (pinfunction "1_1") (pintype "passive"))
      (node (ref "R15") (pin "2") (pinfunction "2_2") (pintype "passive"))
      (node (ref "U2") (pin "3") (pinfunction "FB_3") (pintype "passive"))
    )
    (net (code "44") (name "Net-(U2-SW)") (class "Default")
      (node (ref "C27") (pin "2") (pinfunction "2_2") (pintype "passive"))
      (node (ref "L1") (pin "2") (pinfunction "2_2") (pintype "passive"))
      (node (ref "U2") (pin "6") (pinfunction "SW_6") (pintype "passive"))
    )
    (net (code "45") (name "Net-(U3-FB)") (class "Default")
      (node (ref "C31") (pin "1") (pinfunction "1_1") (pintype "passive"))
      (node (ref "R17") (pin "1") (pinfunction "1_1") (pintype "passive"))
      (node (ref "R18") (pin "2") (pinfunction "2_2") (pintype "passive"))
      (node (ref "U3") (pin "5") (pinfunction "FB_5") (pintype "passive"))
    )
    (net (code "46") (name "Net-(U3-LX)") (class "Default")
      (node (ref "L2") (pin "1") (pinfunction "1_1") (pintype "passive"))
      (node (ref "U3") (pin "3") (pinfunction "LX_3") (pintype "passive"))
    )
    (net (code "47") (name "Net-(U4-RXD)") (class "Default")
      (node (ref "R22") (pin "2") (pinfunction "2_2") (pintype "passive"))
      (node (ref "U4") (pin "4") (pinfunction "RXD_4") (pintype "passive"))
    )
    (net (code "48") (name "VCC") (class "Default")
      (node (ref "C17") (pin "1") (pinfunction "1_1") (pintype "passive"))
      (node (ref "C28") (pin "1") (pinfunction "1_1") (pintype "passive"))
      (node (ref "C29") (pin "1") (pinfunction "1_1") (pintype "passive"))
      (node (ref "D1") (pin "1") (pinfunction "K_1") (pintype "passive"))
      (node (ref "I1") (pin "2") (pinfunction "2_2") (pintype "passive"))
      (node (ref "U2") (pin "4") (pinfunction "EN_4") (pintype "passive"))
      (node (ref "U2") (pin "5") (pinfunction "IN_5") (pintype "passive"))
    )
    (net (code "49") (name "unconnected-(I1-Pad3)") (class "Default")
      (node (ref "I1") (pin "3") (pinfunction "3_3") (pintype "passive"))
    )
    (net (code "50") (name "unconnected-(I1-Pad4)") (class "Default")
      (node (ref "I1") (pin "4") (pinfunction "4_4") (pintype "passive"))
    )
    (net (code "51") (name "unconnected-(S1-Pad2)") (class "Default")
      (node (ref "S1") (pin "2") (pinfunction "2_2") (pintype "passive"))
    )
    (net (code "52") (name "unconnected-(S1-Pad3)") (class "Default")
      (node (ref "S1") (pin "3") (pinfunction "3_3") (pintype "passive"))
    )
    (net (code "53") (name "unconnected-(U1-PA0-Pad34)") (class "Default")
      (node (ref "U1") (pin "34") (pinfunction "PA0_34") (pintype "passive"))
    )
    (net (code "54") (name "unconnected-(U1-PA1-Pad35)") (class "Default")
      (node (ref "U1") (pin "35") (pinfunction "PA1_35") (pintype "passive"))
    )
    (net (code "55") (name "unconnected-(U1-PA2-Pad36)") (class "Default")
      (node (ref "U1") (pin "36") (pinfunction "PA2_36") (pintype "passive"))
    )
    (net (code "56") (name "unconnected-(U1-PA3-Pad37)") (class "Default")
      (node (ref "U1") (pin "37") (pinfunction "PA3_37") (pintype "passive"))
    )
    (net (code "57") (name "unconnected-(U1-PA4-Pad40)") (class "Default")
      (node (ref "U1") (pin "40") (pinfunction "PA4_40") (pintype "passive"))
    )
    (net (code "58") (name "unconnected-(U1-PA8-Pad100)") (class "Default")
      (node (ref "U1") (pin "100") (pinfunction "PA8_100") (pintype "passive"))
    )
    (net (code "59") (name "unconnected-(U1-PA15-Pad110)") (class "Default")
      (node (ref "U1") (pin "110") (pinfunction "PA15_110") (pintype "passive"))
    )
    (net (code "60") (name "unconnected-(U1-PB0-Pad46)") (class "Default")
      (node (ref "U1") (pin "46") (pinfunction "PB0_46") (pintype "passive"))
    )
    (net (code "61") (name "unconnected-(U1-PB1-Pad47)") (class "Default")
      (node (ref "U1") (pin "47") (pinfunction "PB1_47") (pintype "passive"))
    )
    (net (code "62") (name "unconnected-(U1-PB2-Pad48)") (class "Default")
      (node (ref "U1") (pin "48") (pinfunction "PB2_48") (pintype "passive"))
    )
    (net (code "63") (name "unconnected-(U1-PB3-Pad133)") (class "Default")
      (node (ref "U1") (pin "133") (pinfunction "PB3_133") (pintype "passive"))
    )
    (net (code "64") (name "unconnected-(U1-PB4-Pad134)") (class "Default")
      (node (ref "U1") (pin "134") (pinfunction "PB4_134") (pintype "passive"))
    )
    (net (code "65") (name "unconnected-(U1-PB5-Pad135)") (class "Default")
      (node (ref "U1") (pin "135") (pinfunction "PB5_135") (pintype "passive"))
    )
    (net (code "66") (name "unconnected-(U1-PB8-Pad139)") (class "Default")
      (node (ref "U1") (pin "139") (pinfunction "PB8_139") (pintype "passive"))
    )
    (net (code "67") (name "unconnected-(U1-PB9-Pad140)") (class "Default")
      (node (ref "U1") (pin "140") (pinfunction "PB9_140") (pintype "passive"))
    )
    (net (code "68") (name "unconnected-(U1-PB10-Pad69)") (class "Default")
      (node (ref "U1") (pin "69") (pinfunction "PB10_69") (pintype "passive"))
    )
    (net (code "69") (name "unconnected-(U1-PB11-Pad70)") (class "Default")
      (node (ref "U1") (pin "70") (pinfunction "PB11_70") (pintype "passive"))
    )
    (net (code "70") (name "unconnected-(U1-PB12-Pad73)") (class "Default")
      (node (ref "U1") (pin "73") (pinfunction "PB12_73") (pintype "passive"))
    )
    (net (code "71") (name "unconnected-(U1-PB13-Pad74)") (class "Default")
      (node (ref "U1") (pin "74") (pinfunction "PB13_74") (pintype "passive"))
    )
    (net (code "72") (name "unconnected-(U1-PB14-Pad75)") (class "Default")
      (node (ref "U1") (pin "75") (pinfunction "PB14_75") (pintype "passive"))
    )
    (net (code "73") (name "unconnected-(U1-PB15-Pad76)") (class "Default")
      (node (ref "U1") (pin "76") (pinfunction "PB15_76") (pintype "passive"))
    )
    (net (code "74") (name "unconnected-(U1-PC0-Pad26)") (class "Default")
      (node (ref "U1") (pin "26") (pinfunction "PC0_26") (pintype "passive"))
    )
    (net (code "75") (name "unconnected-(U1-PC1-Pad27)") (class "Default")
      (node (ref "U1") (pin "27") (pinfunction "PC1_27") (pintype "passive"))
    )
    (net (code "76") (name "unconnected-(U1-PC2-Pad28)") (class "Default")
      (node (ref "U1") (pin "28") (pinfunction "PC2_28") (pintype "passive"))
    )
    (net (code "77") (name "unconnected-(U1-PC3-Pad29)") (class "Default")
      (node (ref "U1") (pin "29") (pinfunction "PC3_29") (pintype "passive"))
    )
    (net (code "78") (name "unconnected-(U1-PC4-Pad44)") (class "Default")
      (node (ref "U1") (pin "44") (pinfunction "PC4_44") (pintype "passive"))
    )
    (net (code "79") (name "unconnected-(U1-PC5-Pad45)") (class "Default")
      (node (ref "U1") (pin "45") (pinfunction "PC5_45") (pintype "passive"))
    )
    (net (code "80") (name "unconnected-(U1-PC8-Pad98)") (class "Default")
      (node (ref "U1") (pin "98") (pinfunction "PC8_98") (pintype "passive"))
    )
    (net (code "81") (name "unconnected-(U1-PC9-Pad99)") (class "Default")
      (node (ref "U1") (pin "99") (pinfunction "PC9_99") (pintype "passive"))
    )
    (net (code "82") (name "unconnected-(U1-PC10-Pad111)") (class "Default")
      (node (ref "U1") (pin "111") (pinfunction "PC10_111") (pintype "passive"))
    )
    (net (code "83") (name "unconnected-(U1-PC11-Pad112)") (class "Default")
      (node (ref "U1") (pin "112") (pinfunction "PC11_112") (pintype "passive"))
    )
    (net (code "84") (name "unconnected-(U1-PC12-Pad113)") (class "Default")
      (node (ref "U1") (pin "113") (pinfunction "PC12_113") (pintype "passive"))
    )
    (net (code "85") (name "unconnected-(U1-PC13-Pad7)") (class "Default")
      (node (ref "U1") (pin "7") (pinfunction "PC13_7") (pintype "passive"))
    )
    (net (code "86") (name "unconnected-(U1-PC14-Pad8)") (class "Default")
      (node (ref "U1") (pin "8") (pinfunction "PC14_8") (pintype "passive"))
    )
    (net (code "87") (name "unconnected-(U1-PC15-Pad9)") (class "Default")
      (node (ref "U1") (pin "9") (pinfunction "PC15_9") (pintype "passive"))
    )
    (net (code "88") (name "unconnected-(U1-PD0-Pad114)") (class "Default")
      (node (ref "U1") (pin "114") (pinfunction "PD0_114") (pintype "passive"))
    )
    (net (code "89") (name "unconnected-(U1-PD1-Pad115)") (class "Default")
      (node (ref "U1") (pin "115") (pinfunction "PD1_115") (pintype "passive"))
    )
    (net (code "90") (name "unconnected-(U1-PD2-Pad116)") (class "Default")
      (node (ref "U1") (pin "116") (pinfunction "PD2_116") (pintype "passive"))
    )
    (net (code "91") (name "unconnected-(U1-PD3-Pad117)") (class "Default")
      (node (ref "U1") (pin "117") (pinfunction "PD3_117") (pintype "passive"))
    )
    (net (code "92") (name "unconnected-(U1-PD4-Pad118)") (class "Default")
      (node (ref "U1") (pin "118") (pinfunction "PD4_118") (pintype "passive"))
    )
    (net (code "93") (name "unconnected-(U1-PD5-Pad119)") (class "Default")
      (node (ref "U1") (pin "119") (pinfunction "PD5_119") (pintype "passive"))
    )
    (net (code "94") (name "unconnected-(U1-PD6-Pad122)") (class "Default")
      (node (ref "U1") (pin "122") (pinfunction "PD6_122") (pintype "passive"))
    )
    (net (code "95") (name "unconnected-(U1-PD7-Pad123)") (class "Default")
      (node (ref "U1") (pin "123") (pinfunction "PD7_123") (pintype "passive"))
    )
    (net (code "96") (name "unconnected-(U1-PD8-Pad77)") (class "Default")
      (node (ref "U1") (pin "77") (pinfunction "PD8_77") (pintype "passive"))
    )
    (net (code "97") (name "unconnected-(U1-PD9-Pad78)") (class "Default")
      (node (ref "U1") (pin "78") (pinfunction "PD9_78") (pintype "passive"))
    )
    (net (code "98") (name "unconnected-(U1-PD11-Pad80)") (class "Default")
      (node (ref "U1") (pin "80") (pinfunction "PD11_80") (pintype "passive"))
    )
    (net (code "99") (name "unconnected-(U1-PD12-Pad81)") (class "Default")
      (node (ref "U1") (pin "81") (pinfunction "PD12_81") (pintype "passive"))
    )
    (net (code "100") (name "unconnected-(U1-PD13-Pad82)") (class "Default")
      (node (ref "U1") (pin "82") (pinfunction "PD13_82") (pintype "passive"))
    )
    (net (code "101") (name "unconnected-(U1-PD14-Pad85)") (class "Default")
      (node (ref "U1") (pin "85") (pinfunction "PD14_85") (pintype "passive"))
    )
    (net (code "102") (name "unconnected-(U1-PD15-Pad86)") (class "Default")
      (node (ref "U1") (pin "86") (pinfunction "PD15_86") (pintype "passive"))
    )
    (net (code "103") (name "unconnected-(U1-PE0-Pad141)") (class "Default")
      (node (ref "U1") (pin "141") (pinfunction "PE0_141") (pintype "passive"))
    )
    (net (code "104") (name "unconnected-(U1-PE1-Pad142)") (class "Default")
      (node (ref "U1") (pin "142") (pinfunction "PE1_142") (pintype "passive"))
    )
    (net (code "105") (name "unconnected-(U1-PE2-Pad1)") (class "Default")
      (node (ref "U1") (pin "1") (pinfunction "PE2_1") (pintype "passive"))
    )
    (net (code "106") (name "unconnected-(U1-PE3-Pad2)") (class "Default")
      (node (ref "U1") (pin "2") (pinfunction "PE3_2") (pintype "passive"))
    )
    (net (code "107") (name "unconnected-(U1-PE4-Pad3)") (class "Default")
      (node (ref "U1") (pin "3") (pinfunction "PE4_3") (pintype "passive"))
    )
    (net (code "108") (name "unconnected-(U1-PE5-Pad4)") (class "Default")
      (node (ref "U1") (pin "4") (pinfunction "PE5_4") (pintype "passive"))
    )
    (net (code "109") (name "unconnected-(U1-PE6-Pad5)") (class "Default")
      (node (ref "U1") (pin "5") (pinfunction "PE6_5") (pintype "passive"))
    )
    (net (code "110") (name "unconnected-(U1-PE7-Pad58)") (class "Default")
      (node (ref "U1") (pin "58") (pinfunction "PE7_58") (pintype "passive"))
    )
    (net (code "111") (name "unconnected-(U1-PE8-Pad59)") (class "Default")
      (node (ref "U1") (pin "59") (pinfunction "PE8_59") (pintype "passive"))
    )
    (net (code "112") (name "unconnected-(U1-PE10-Pad63)") (class "Default")
      (node (ref "U1") (pin "63") (pinfunction "PE10_63") (pintype "passive"))
    )
    (net (code "113") (name "unconnected-(U1-PE12-Pad65)") (class "Default")
      (node (ref "U1") (pin "65") (pinfunction "PE12_65") (pintype "passive"))
    )
    (net (code "114") (name "unconnected-(U1-PE13-Pad66)") (class "Default")
      (node (ref "U1") (pin "66") (pinfunction "PE13_66") (pintype "passive"))
    )
    (net (code "115") (name "unconnected-(U1-PE14-Pad67)") (class "Default")
      (node (ref "U1") (pin "67") (pinfunction "PE14_67") (pintype "passive"))
    )
    (net (code "116") (name "unconnected-(U1-PE15-Pad68)") (class "Default")
      (node (ref "U1") (pin "68") (pinfunction "PE15_68") (pintype "passive"))
    )
    (net (code "117") (name "unconnected-(U1-PF0-Pad10)") (class "Default")
      (node (ref "U1") (pin "10") (pinfunction "PF0_10") (pintype "passive"))
    )
    (net (code "118") (name "unconnected-(U1-PF1-Pad11)") (class "Default")
      (node (ref "U1") (pin "11") (pinfunction "PF1_11") (pintype "passive"))
    )
    (net (code "119") (name "unconnected-(U1-PF2-Pad12)") (class "Default")
      (node (ref "U1") (pin "12") (pinfunction "PF2_12") (pintype "passive"))
    )
    (net (code "120") (name "unconnected-(U1-PF3-Pad13)") (class "Default")
      (node (ref "U1") (pin "13") (pinfunction "PF3_13") (pintype "passive"))
    )
    (net (code "121") (name "unconnected-(U1-PF4-Pad14)") (class "Default")
      (node (ref "U1") (pin "14") (pinfunction "PF4_14") (pintype "passive"))
    )
    (net (code "122") (name "unconnected-(U1-PF5-Pad15)") (class "Default")
      (node (ref "U1") (pin "15") (pinfunction "PF5_15") (pintype "passive"))
    )
    (net (code "123") (name "unconnected-(U1-PF6-Pad18)") (class "Default")
      (node (ref "U1") (pin "18") (pinfunction "PF6_18") (pintype "passive"))
    )
    (net (code "124") (name "unconnected-(U1-PF7-Pad19)") (class "Default")
      (node (ref "U1") (pin "19") (pinfunction "PF7_19") (pintype "passive"))
    )
    (net (code "125") (name "unconnected-(U1-PF8-Pad20)") (class "Default")
      (node (ref "U1") (pin "20") (pinfunction "PF8_20") (pintype "passive"))
    )
    (net (code "126") (name "unconnected-(U1-PF9-Pad21)") (class "Default")
      (node (ref "U1") (pin "21") (pinfunction "PF9_21") (pintype "passive"))
    )
    (net (code "127") (name "unconnected-(U1-PF10-Pad22)") (class "Default")
      (node (ref "U1") (pin "22") (pinfunction "PF10_22") (pintype "passive"))
    )
    (net (code "128") (name "unconnected-(U1-PF11-Pad49)") (class "Default")
      (node (ref "U1") (pin "49") (pinfunction "PF11_49") (pintype "passive"))
    )
    (net (code "129") (name "unconnected-(U1-PF12-Pad50)") (class "Default")
      (node (ref "U1") (pin "50") (pinfunction "PF12_50") (pintype "passive"))
    )
    (net (code "130") (name "unconnected-(U1-PF13-Pad53)") (class "Default")
      (node (ref "U1") (pin "53") (pinfunction "PF13_53") (pintype "passive"))
    )
    (net (code "131") (name "unconnected-(U1-PF14-Pad54)") (class "Default")
      (node (ref "U1") (pin "54") (pinfunction "PF14_54") (pintype "passive"))
    )
    (net (code "132") (name "unconnected-(U1-PF15-Pad55)") (class "Default")
      (node (ref "U1") (pin "55") (pinfunction "PF15_55") (pintype "passive"))
    )
    (net (code "133") (name "unconnected-(U1-PG0-Pad56)") (class "Default")
      (node (ref "U1") (pin "56") (pinfunction "PG0_56") (pintype "passive"))
    )
    (net (code "134") (name "unconnected-(U1-PG1-Pad57)") (class "Default")
      (node (ref "U1") (pin "57") (pinfunction "PG1_57") (pintype "passive"))
    )
    (net (code "135") (name "unconnected-(U1-PG2-Pad87)") (class "Default")
      (node (ref "U1") (pin "87") (pinfunction "PG2_87") (pintype "passive"))
    )
    (net (code "136") (name "unconnected-(U1-PG3-Pad88)") (class "Default")
      (node (ref "U1") (pin "88") (pinfunction "PG3_88") (pintype "passive"))
    )
    (net (code "137") (name "unconnected-(U1-PG4-Pad89)") (class "Default")
      (node (ref "U1") (pin "89") (pinfunction "PG4_89") (pintype "passive"))
    )
    (net (code "138") (name "unconnected-(U1-PG5-Pad90)") (class "Default")
      (node (ref "U1") (pin "90") (pinfunction "PG5_90") (pintype "passive"))
    )
    (net (code "139") (name "unconnected-(U1-PG6-Pad91)") (class "Default")
      (node (ref "U1") (pin "91") (pinfunction "PG6_91") (pintype "passive"))
    )
    (net (code "140") (name "unconnected-(U1-PG7-Pad92)") (class "Default")
      (node (ref "U1") (pin "92") (pinfunction "PG7_92") (pintype "passive"))
    )
    (net (code "141") (name "unconnected-(U1-PG8-Pad93)") (class "Default")
      (node (ref "U1") (pin "93") (pinfunction "PG8_93") (pintype "passive"))
    )
    (net (code "142") (name "unconnected-(U1-PG9-Pad124)") (class "Default")
      (node (ref "U1") (pin "124") (pinfunction "PG9_124") (pintype "passive"))
    )
    (net (code "143") (name "unconnected-(U1-PG10-Pad125)") (class "Default")
      (node (ref "U1") (pin "125") (pinfunction "PG10_125") (pintype "passive"))
    )
    (net (code "144") (name "unconnected-(U1-PG11-Pad126)") (class "Default")
      (node (ref "U1") (pin "126") (pinfunction "PG11_126") (pintype "passive"))
    )
    (net (code "145") (name "unconnected-(U1-PG12-Pad127)") (class "Default")
      (node (ref "U1") (pin "127") (pinfunction "PG12_127") (pintype "passive"))
    )
    (net (code "146") (name "unconnected-(U1-PG13-Pad128)") (class "Default")
      (node (ref "U1") (pin "128") (pinfunction "PG13_128") (pintype "passive"))
    )
    (net (code "147") (name "unconnected-(U1-PG14-Pad129)") (class "Default")
      (node (ref "U1") (pin "129") (pinfunction "PG14_129") (pintype "passive"))
    )
    (net (code "148") (name "unconnected-(U1-PG15-Pad132)") (class "Default")
      (node (ref "U1") (pin "132") (pinfunction "PG15_132") (pintype "passive"))
    )
  )
)
